# MICROCONTROLLER.net
KiCad netlist of a schematic drawn in Altium Designer
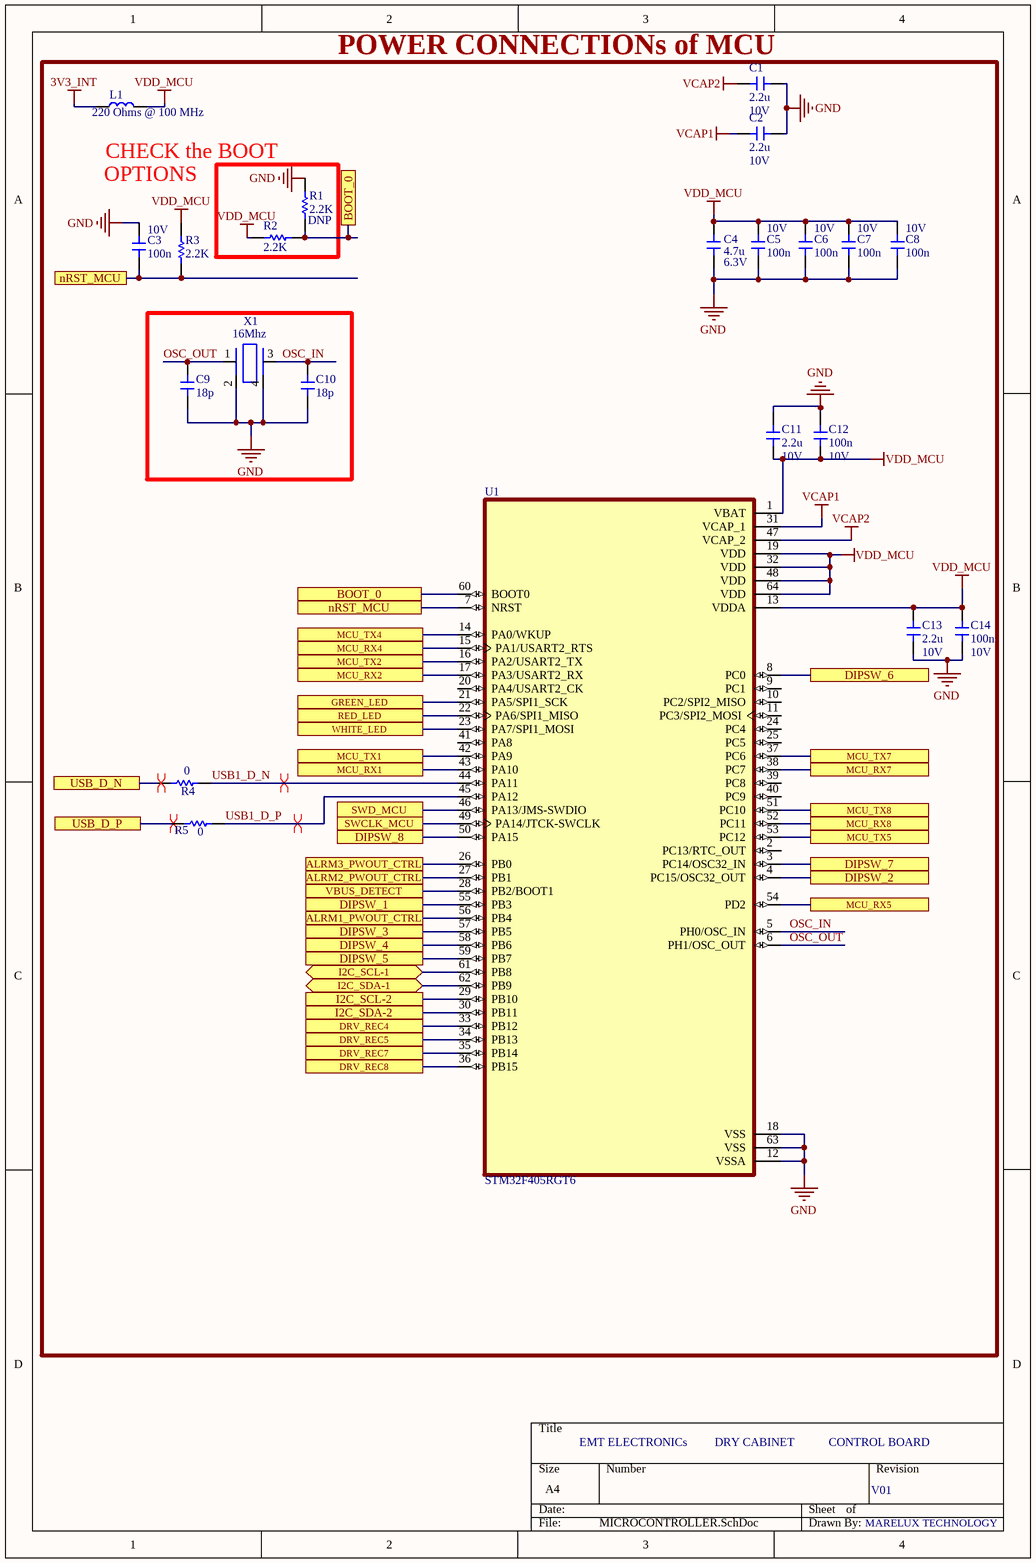
[diagram p0: MICROCONTROLLER.SchDoc]

(export (version "E")
  (design (tool "Eeschema 10.0.6"))
  (components
    (comp (ref "C1")
      (value "2.2u")
      (footprint "CAP_0603_CER")
      (description "Generic")
      (fields (field (name "PART NUMBER") "CL10A225KP8NNNC") (field (name "VOLTAGE") "10V"))
      (libsource (lib "MareLux24Lib") (part "CAP_GEN_CER"))
    )
    (comp (ref "C2")
      (value "2.2u")
      (footprint "CAP_0603_CER")
      (description "Generic")
      (fields (field (name "PART NUMBER") "CL10A225KP8NNNC") (field (name "VOLTAGE") "10V"))
      (libsource (lib "MareLux24Lib") (part "CAP_GEN_CER"))
    )
    (comp (ref "C3")
      (value "100n")
      (footprint "CAP_0402_CER")
      (description "Generic")
      (fields (field (name "PART NUMBER") "CL05B104KP5NNNC") (field (name "VOLTAGE") "10V"))
      (libsource (lib "MareLux24Lib") (part "CAP_GEN_CER"))
    )
    (comp (ref "C4")
      (value "4.7u")
      (footprint "CAP_0603_CER")
      (description "Generic")
      (fields (field (name "PART NUMBER") "CL10A475KP8NNNC") (field (name "VOLTAGE") "6.3V"))
      (libsource (lib "MareLux24Lib") (part "CAP_GEN_CER"))
    )
    (comp (ref "C5")
      (value "100n")
      (footprint "CAP_0402_CER")
      (description "Generic")
      (fields (field (name "PART NUMBER") "CL05B104KP5NNNC") (field (name "VOLTAGE") "10V"))
      (libsource (lib "MareLux24Lib") (part "CAP_GEN_CER"))
    )
    (comp (ref "C6")
      (value "100n")
      (footprint "CAP_0402_CER")
      (description "Generic")
      (fields (field (name "PART NUMBER") "CL05B104KP5NNNC") (field (name "VOLTAGE") "10V"))
      (libsource (lib "MareLux24Lib") (part "CAP_GEN_CER"))
    )
    (comp (ref "C7")
      (value "100n")
      (footprint "CAP_0402_CER")
      (description "Generic")
      (fields (field (name "PART NUMBER") "CL05B104KP5NNNC") (field (name "VOLTAGE") "10V"))
      (libsource (lib "MareLux24Lib") (part "CAP_GEN_CER"))
    )
    (comp (ref "C8")
      (value "100n")
      (footprint "CAP_0402_CER")
      (description "Generic")
      (fields (field (name "PART NUMBER") "CL05B104KP5NNNC") (field (name "VOLTAGE") "10V"))
      (libsource (lib "MareLux24Lib") (part "CAP_GEN_CER"))
    )
    (comp (ref "C9")
      (value "18p")
      (footprint "CAP_0402_CER")
      (description "Generic")
      (fields (field (name "PART NUMBER") "CC0402JRNPO9BN180"))
      (libsource (lib "MareLux24Lib") (part "CAP_GEN_CER"))
    )
    (comp (ref "C10")
      (value "18p")
      (footprint "CAP_0402_CER")
      (description "Generic")
      (fields (field (name "PART NUMBER") "CC0402JRNPO9BN180"))
      (libsource (lib "MareLux24Lib") (part "CAP_GEN_CER"))
    )
    (comp (ref "C11")
      (value "2.2u")
      (footprint "CAP_0603_CER")
      (description "Generic")
      (fields (field (name "PART NUMBER") "CL10A225KP8NNNC") (field (name "VOLTAGE") "10V"))
      (libsource (lib "MareLux24Lib") (part "CAP_GEN_CER"))
    )
    (comp (ref "C12")
      (value "100n")
      (footprint "CAP_0402_CER")
      (description "Generic")
      (fields (field (name "PART NUMBER") "CL05B104KP5NNNC") (field (name "VOLTAGE") "10V"))
      (libsource (lib "MareLux24Lib") (part "CAP_GEN_CER"))
    )
    (comp (ref "C13")
      (value "2.2u")
      (footprint "CAP_0603_CER")
      (description "Generic")
      (fields (field (name "PART NUMBER") "CL10A225KP8NNNC") (field (name "VOLTAGE") "10V"))
      (libsource (lib "MareLux24Lib") (part "CAP_GEN_CER"))
    )
    (comp (ref "C14")
      (value "100n")
      (footprint "CAP_0402_CER")
      (description "Generic")
      (fields (field (name "PART NUMBER") "CL05B104KP5NNNC") (field (name "VOLTAGE") "10V"))
      (libsource (lib "MareLux24Lib") (part "CAP_GEN_CER"))
    )
    (comp (ref "L1")
      (value "220 Ohms @ 100 MHz")
      (footprint "IND_0603_SMD")
      (description "Generic SMD IND/BEAD")
      (fields (field (name "PART NUMBER") "MPZ1608S221ATA00"))
      (libsource (lib "MareLux24Lib") (part "IND_GEN_SMD"))
    )
    (comp (ref "R1")
      (value "2.2K")
      (footprint "RES_0402_SMD")
      (description "Generic Chip Res")
      (fields (field (name "PART NUMBER") "RMCF0402JT2K20") (field (name "PLACE") "DNP"))
      (libsource (lib "MareLux24Lib") (part "RES_GEN_SMD"))
    )
    (comp (ref "R2")
      (value "2.2K")
      (footprint "RES_0402_SMD")
      (description "Generic Chip Res")
      (fields (field (name "PART NUMBER") "RMCF0402JT2K20"))
      (libsource (lib "MareLux24Lib") (part "RES_GEN_SMD"))
    )
    (comp (ref "R3")
      (value "2.2K")
      (footprint "RES_0402_SMD")
      (description "Generic Chip Res")
      (fields (field (name "PART NUMBER") "RMCF0402JT2K20"))
      (libsource (lib "MareLux24Lib") (part "RES_GEN_SMD"))
    )
    (comp (ref "R4")
      (value "0")
      (footprint "RES_0402_SMD")
      (description "Generic Chip Res")
      (fields (field (name "PART NUMBER") "RC0402JR-070RL"))
      (libsource (lib "MareLux24Lib") (part "RES_GEN_SMD"))
    )
    (comp (ref "R5")
      (value "0")
      (footprint "RES_0402_SMD")
      (description "Generic Chip Res")
      (fields (field (name "PART NUMBER") "RC0402JR-070RL"))
      (libsource (lib "MareLux24Lib") (part "RES_GEN_SMD"))
    )
    (comp (ref "U1")
      (value "STM32F405RGT6")
      (footprint "LQFP64-10x10mm")
      (libsource (lib "STM32F405RGT6") (part "STM32F405RGT6"))
    )
    (comp (ref "X1")
      (value "16Mhz")
      (footprint "XTAL-4SMD")
      (description "16 MHz ±10ppm Crystal 9pF 40 Ohms 4-SMD, No Lead")
      (fields (field (name "TOLERANCE") "±10ppm") (field (name "PART NUMBER") "CF4016M00009T1521005"))
      (libsource (lib "MareLux24Lib") (part "XTAL-4PINs"))
    )
  )
  (nets
    (net (code "1") (name "/ALRM1_PWOUT_CTRL") (class "Default")
      (node (ref "U1") (pin "56") (pinfunction "PB4_56") (pintype "bidirectional"))
    )
    (net (code "2") (name "/ALRM2_PWOUT_CTRL") (class "Default")
      (node (ref "U1") (pin "27") (pinfunction "PB1_27") (pintype "bidirectional"))
    )
    (net (code "3") (name "/ALRM3_PWOUT_CTRL") (class "Default")
      (node (ref "U1") (pin "26") (pinfunction "PB0_26") (pintype "bidirectional"))
    )
    (net (code "4") (name "/BOOT_0") (class "Default")
      (node (ref "R1") (pin "1") (pinfunction "1_1") (pintype "passive"))
      (node (ref "R2") (pin "1") (pinfunction "1_1") (pintype "passive"))
      (node (ref "U1") (pin "60") (pinfunction "BOOT0_60") (pintype "bidirectional"))
    )
    (net (code "5") (name "/DIPSW_1") (class "Default")
      (node (ref "U1") (pin "55") (pinfunction "PB3_55") (pintype "bidirectional"))
    )
    (net (code "6") (name "/DIPSW_2") (class "Default")
      (node (ref "U1") (pin "4") (pinfunction "PC15/OSC32_OUT_4") (pintype "bidirectional"))
    )
    (net (code "7") (name "/DIPSW_3") (class "Default")
      (node (ref "U1") (pin "57") (pinfunction "PB5_57") (pintype "bidirectional"))
    )
    (net (code "8") (name "/DIPSW_4") (class "Default")
      (node (ref "U1") (pin "58") (pinfunction "PB6_58") (pintype "bidirectional"))
    )
    (net (code "9") (name "/DIPSW_5") (class "Default")
      (node (ref "U1") (pin "59") (pinfunction "PB7_59") (pintype "bidirectional"))
    )
    (net (code "10") (name "/DIPSW_6") (class "Default")
      (node (ref "U1") (pin "8") (pinfunction "PC0_8") (pintype "bidirectional"))
    )
    (net (code "11") (name "/DIPSW_7") (class "Default")
      (node (ref "U1") (pin "3") (pinfunction "PC14/OSC32_IN_3") (pintype "bidirectional"))
    )
    (net (code "12") (name "/DIPSW_8") (class "Default")
      (node (ref "U1") (pin "50") (pinfunction "PA15_50") (pintype "bidirectional"))
    )
    (net (code "13") (name "/DRV_REC4") (class "Default")
      (node (ref "U1") (pin "33") (pinfunction "PB12_33") (pintype "bidirectional"))
    )
    (net (code "14") (name "/DRV_REC5") (class "Default")
      (node (ref "U1") (pin "34") (pinfunction "PB13_34") (pintype "bidirectional"))
    )
    (net (code "15") (name "/DRV_REC7") (class "Default")
      (node (ref "U1") (pin "35") (pinfunction "PB14_35") (pintype "bidirectional"))
    )
    (net (code "16") (name "/DRV_REC8") (class "Default")
      (node (ref "U1") (pin "36") (pinfunction "PB15_36") (pintype "bidirectional"))
    )
    (net (code "17") (name "/GREEN_LED") (class "Default")
      (node (ref "U1") (pin "21") (pinfunction "PA5/SPI1_SCK_21") (pintype "bidirectional"))
    )
    (net (code "18") (name "/I2C_SCL-1") (class "Default")
      (node (ref "U1") (pin "61") (pinfunction "PB8_61") (pintype "bidirectional"))
    )
    (net (code "19") (name "/I2C_SCL-2") (class "Default")
      (node (ref "U1") (pin "29") (pinfunction "PB10_29") (pintype "bidirectional"))
    )
    (net (code "20") (name "/I2C_SDA-1") (class "Default")
      (node (ref "U1") (pin "62") (pinfunction "PB9_62") (pintype "bidirectional"))
    )
    (net (code "21") (name "/I2C_SDA-2") (class "Default")
      (node (ref "U1") (pin "30") (pinfunction "PB11_30") (pintype "bidirectional"))
    )
    (net (code "22") (name "/MCU_RX1") (class "Default")
      (node (ref "U1") (pin "43") (pinfunction "PA10_43") (pintype "bidirectional"))
    )
    (net (code "23") (name "/MCU_RX2") (class "Default")
      (node (ref "U1") (pin "17") (pinfunction "PA3/USART2_RX_17") (pintype "bidirectional"))
    )
    (net (code "24") (name "/MCU_RX4") (class "Default")
      (node (ref "U1") (pin "15") (pinfunction "PA1/USART2_RTS_15") (pintype "bidirectional"))
    )
    (net (code "25") (name "/MCU_RX5") (class "Default")
      (node (ref "U1") (pin "54") (pinfunction "PD2_54") (pintype "bidirectional"))
    )
    (net (code "26") (name "/MCU_RX7") (class "Default")
      (node (ref "U1") (pin "38") (pinfunction "PC7_38") (pintype "bidirectional"))
    )
    (net (code "27") (name "/MCU_RX8") (class "Default")
      (node (ref "U1") (pin "52") (pinfunction "PC11_52") (pintype "bidirectional"))
    )
    (net (code "28") (name "/MCU_TX1") (class "Default")
      (node (ref "U1") (pin "42") (pinfunction "PA9_42") (pintype "bidirectional"))
    )
    (net (code "29") (name "/MCU_TX2") (class "Default")
      (node (ref "U1") (pin "16") (pinfunction "PA2/USART2_TX_16") (pintype "bidirectional"))
    )
    (net (code "30") (name "/MCU_TX4") (class "Default")
      (node (ref "U1") (pin "14") (pinfunction "PA0/WKUP_14") (pintype "bidirectional"))
    )
    (net (code "31") (name "/MCU_TX5") (class "Default")
      (node (ref "U1") (pin "53") (pinfunction "PC12_53") (pintype "bidirectional"))
    )
    (net (code "32") (name "/MCU_TX7") (class "Default")
      (node (ref "U1") (pin "37") (pinfunction "PC6_37") (pintype "bidirectional"))
    )
    (net (code "33") (name "/MCU_TX8") (class "Default")
      (node (ref "U1") (pin "51") (pinfunction "PC10_51") (pintype "bidirectional"))
    )
    (net (code "34") (name "/OSC_IN") (class "Default")
      (node (ref "C10") (pin "1") (pinfunction "1_1") (pintype "passive"))
      (node (ref "U1") (pin "5") (pinfunction "PH0/OSC_IN_5") (pintype "bidirectional"))
      (node (ref "X1") (pin "3") (pinfunction "3_3") (pintype "passive"))
    )
    (net (code "35") (name "/OSC_OUT") (class "Default")
      (node (ref "C9") (pin "1") (pinfunction "1_1") (pintype "passive"))
      (node (ref "U1") (pin "6") (pinfunction "PH1/OSC_OUT_6") (pintype "bidirectional"))
      (node (ref "X1") (pin "1") (pinfunction "0_1") (pintype "passive"))
    )
    (net (code "36") (name "/RED_LED") (class "Default")
      (node (ref "U1") (pin "22") (pinfunction "PA6/SPI1_MISO_22") (pintype "bidirectional"))
    )
    (net (code "37") (name "/SWCLK_MCU") (class "Default")
      (node (ref "U1") (pin "49") (pinfunction "PA14/JTCK-SWCLK_49") (pintype "bidirectional"))
    )
    (net (code "38") (name "/SWD_MCU") (class "Default")
      (node (ref "U1") (pin "46") (pinfunction "PA13/JMS-SWDIO_46") (pintype "bidirectional"))
    )
    (net (code "39") (name "/USB1_D_N") (class "Default")
      (node (ref "R4") (pin "2") (pinfunction "2_2") (pintype "passive"))
      (node (ref "U1") (pin "44") (pinfunction "PA11_44") (pintype "bidirectional"))
    )
    (net (code "40") (name "/USB1_D_P") (class "Default")
      (node (ref "R5") (pin "2") (pinfunction "2_2") (pintype "passive"))
      (node (ref "U1") (pin "45") (pinfunction "PA12_45") (pintype "bidirectional"))
    )
    (net (code "41") (name "/USB_D_N") (class "Default")
      (node (ref "R4") (pin "1") (pinfunction "1_1") (pintype "passive"))
    )
    (net (code "42") (name "/USB_D_P") (class "Default")
      (node (ref "R5") (pin "1") (pinfunction "1_1") (pintype "passive"))
    )
    (net (code "43") (name "/VBUS_DETECT") (class "Default")
      (node (ref "U1") (pin "28") (pinfunction "PB2/BOOT1_28") (pintype "bidirectional"))
    )
    (net (code "44") (name "/WHITE_LED") (class "Default")
      (node (ref "U1") (pin "23") (pinfunction "PA7/SPI1_MOSI_23") (pintype "bidirectional"))
    )
    (net (code "45") (name "/nRST_MCU") (class "Default")
      (node (ref "C3") (pin "2") (pinfunction "2_2") (pintype "passive"))
      (node (ref "R3") (pin "2") (pinfunction "2_2") (pintype "passive"))
      (node (ref "U1") (pin "7") (pinfunction "NRST_7") (pintype "bidirectional"))
    )
    (net (code "46") (name "3V3_INT") (class "Default")
      (node (ref "L1") (pin "1") (pinfunction "1_1") (pintype "passive"))
    )
    (net (code "47") (name "GND") (class "Default")
      (node (ref "C1") (pin "1") (pinfunction "1_1") (pintype "passive"))
      (node (ref "C10") (pin "2") (pinfunction "2_2") (pintype "passive"))
      (node (ref "C11") (pin "2") (pinfunction "2_2") (pintype "passive"))
      (node (ref "C12") (pin "1") (pinfunction "1_1") (pintype "passive"))
      (node (ref "C13") (pin "1") (pinfunction "1_1") (pintype "passive"))
      (node (ref "C14") (pin "2") (pinfunction "2_2") (pintype "passive"))
      (node (ref "C2") (pin "1") (pinfunction "1_1") (pintype "passive"))
      (node (ref "C3") (pin "1") (pinfunction "1_1") (pintype "passive"))
      (node (ref "C4") (pin "1") (pinfunction "1_1") (pintype "passive"))
      (node (ref "C5") (pin "2") (pinfunction "2_2") (pintype "passive"))
      (node (ref "C6") (pin "2") (pinfunction "2_2") (pintype "passive"))
      (node (ref "C7") (pin "2") (pinfunction "2_2") (pintype "passive"))
      (node (ref "C8") (pin "2") (pinfunction "2_2") (pintype "passive"))
      (node (ref "C9") (pin "2") (pinfunction "2_2") (pintype "passive"))
      (node (ref "R1") (pin "2") (pinfunction "2_2") (pintype "passive"))
      (node (ref "U1") (pin "12") (pinfunction "VSSA_12") (pintype "power_in"))
      (node (ref "U1") (pin "18") (pinfunction "VSS_18") (pintype "power_in"))
      (node (ref "U1") (pin "63") (pinfunction "VSS_63") (pintype "power_in"))
      (node (ref "X1") (pin "2") (pinfunction "2_2") (pintype "passive"))
      (node (ref "X1") (pin "4") (pinfunction "4_4") (pintype "passive"))
    )
    (net (code "48") (name "VCAP1") (class "Default")
      (node (ref "C2") (pin "2") (pinfunction "2_2") (pintype "passive"))
      (node (ref "U1") (pin "31") (pinfunction "VCAP_1_31") (pintype "power_in"))
    )
    (net (code "49") (name "VCAP2") (class "Default")
      (node (ref "C1") (pin "2") (pinfunction "2_2") (pintype "passive"))
      (node (ref "U1") (pin "47") (pinfunction "VCAP_2_47") (pintype "power_in"))
    )
    (net (code "50") (name "VDD_MCU") (class "Default")
      (node (ref "C11") (pin "1") (pinfunction "1_1") (pintype "passive"))
      (node (ref "C12") (pin "2") (pinfunction "2_2") (pintype "passive"))
      (node (ref "C13") (pin "2") (pinfunction "2_2") (pintype "passive"))
      (node (ref "C14") (pin "1") (pinfunction "1_1") (pintype "passive"))
      (node (ref "C4") (pin "2") (pinfunction "2_2") (pintype "passive"))
      (node (ref "C5") (pin "1") (pinfunction "1_1") (pintype "passive"))
      (node (ref "C6") (pin "1") (pinfunction "1_1") (pintype "passive"))
      (node (ref "C7") (pin "1") (pinfunction "1_1") (pintype "passive"))
      (node (ref "C8") (pin "1") (pinfunction "1_1") (pintype "passive"))
      (node (ref "L1") (pin "2") (pinfunction "2_2") (pintype "passive"))
      (node (ref "R2") (pin "2") (pinfunction "2_2") (pintype "passive"))
      (node (ref "R3") (pin "1") (pinfunction "1_1") (pintype "passive"))
      (node (ref "U1") (pin "1") (pinfunction "VBAT_1") (pintype "power_in"))
      (node (ref "U1") (pin "13") (pinfunction "VDDA_13") (pintype "power_in"))
      (node (ref "U1") (pin "19") (pinfunction "VDD_19") (pintype "power_in"))
      (node (ref "U1") (pin "32") (pinfunction "VDD_32") (pintype "power_in"))
      (node (ref "U1") (pin "48") (pinfunction "VDD_48") (pintype "power_in"))
      (node (ref "U1") (pin "64") (pinfunction "VDD_64") (pintype "power_in"))
    )
    (net (code "51") (name "unconnected-(U1-PA4{slash}USART2_CK-Pad20)") (class "Default")
      (node (ref "U1") (pin "20") (pinfunction "PA4/USART2_CK_20") (pintype "bidirectional"))
    )
    (net (code "52") (name "unconnected-(U1-PA8-Pad41)") (class "Default")
      (node (ref "U1") (pin "41") (pinfunction "PA8_41") (pintype "bidirectional"))
    )
    (net (code "53") (name "unconnected-(U1-PC1-Pad9)") (class "Default")
      (node (ref "U1") (pin "9") (pinfunction "PC1_9") (pintype "bidirectional"))
    )
    (net (code "54") (name "unconnected-(U1-PC2{slash}SPI2_MISO-Pad10)") (class "Default")
      (node (ref "U1") (pin "10") (pinfunction "PC2/SPI2_MISO_10") (pintype "bidirectional"))
    )
    (net (code "55") (name "unconnected-(U1-PC3{slash}SPI2_MOSI-Pad11)") (class "Default")
      (node (ref "U1") (pin "11") (pinfunction "PC3/SPI2_MOSI_11") (pintype "bidirectional"))
    )
    (net (code "56") (name "unconnected-(U1-PC4-Pad24)") (class "Default")
      (node (ref "U1") (pin "24") (pinfunction "PC4_24") (pintype "bidirectional"))
    )
    (net (code "57") (name "unconnected-(U1-PC5-Pad25)") (class "Default")
      (node (ref "U1") (pin "25") (pinfunction "PC5_25") (pintype "bidirectional"))
    )
    (net (code "58") (name "unconnected-(U1-PC8-Pad39)") (class "Default")
      (node (ref "U1") (pin "39") (pinfunction "PC8_39") (pintype "bidirectional"))
    )
    (net (code "59") (name "unconnected-(U1-PC9-Pad40)") (class "Default")
      (node (ref "U1") (pin "40") (pinfunction "PC9_40") (pintype "bidirectional"))
    )
    (net (code "60") (name "unconnected-(U1-PC13{slash}RTC_OUT-Pad2)") (class "Default")
      (node (ref "U1") (pin "2") (pinfunction "PC13/RTC_OUT_2") (pintype "bidirectional"))
    )
  )
)
